# STM32F1_DHT11_UART.net
KiCad netlist of a schematic drawn in Altium Designer
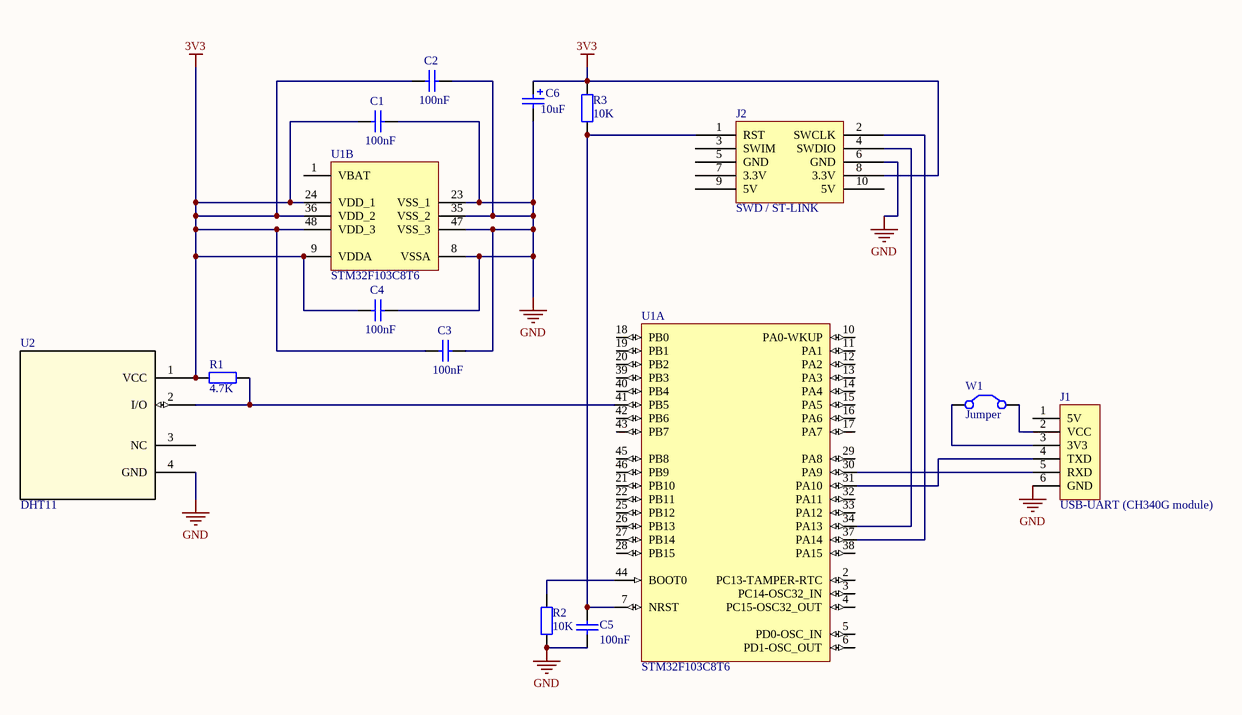
[diagram p0: STM32F1 DHT11 UART.SchDoc]

(export (version "E")
  (design (tool "Eeschema 10.0.6"))
  (components
    (comp (ref "C1")
      (value "100nF")
      (footprint "C1206")
      (description "Capacitor (Semiconductor SIM Model)")
      (fields (field (name "PUBLISHER") "Altium Limited"))
      (libsource (lib "Miscellaneous Devices") (part "Cap Semi"))
    )
    (comp (ref "C2")
      (value "100nF")
      (footprint "C1206")
      (description "Capacitor (Semiconductor SIM Model)")
      (fields (field (name "PUBLISHER") "Altium Limited"))
      (libsource (lib "Miscellaneous Devices") (part "Cap Semi"))
    )
    (comp (ref "C3")
      (value "100nF")
      (footprint "C1206")
      (description "Capacitor (Semiconductor SIM Model)")
      (fields (field (name "PUBLISHER") "Altium Limited"))
      (libsource (lib "Miscellaneous Devices") (part "Cap Semi"))
    )
    (comp (ref "C4")
      (value "100nF")
      (footprint "C1206")
      (description "Capacitor (Semiconductor SIM Model)")
      (fields (field (name "PUBLISHER") "Altium Limited"))
      (libsource (lib "Miscellaneous Devices") (part "Cap Semi"))
    )
    (comp (ref "C5")
      (value "100nF")
      (footprint "C1206")
      (description "Capacitor (Semiconductor SIM Model)")
      (fields (field (name "PUBLISHER") "Altium Limited"))
      (libsource (lib "Miscellaneous Devices") (part "Cap Semi"))
    )
    (comp (ref "C6")
      (value "~")
      (footprint "POLAR0.8")
      (description "Polarized Capacitor (Axial)")
      (fields (field (name "ALTIUM_UNNAMED_1") "10uF") (field (name "PUBLISHER") "Altium Limited"))
      (libsource (lib "Miscellaneous Devices") (part "Cap Pol2"))
    )
    (comp (ref "J1")
      (value "USB-UART (CH340G module)")
      (footprint "HDR1X6")
      (description "Header, 6-Pin")
      (fields (field (name "PUBLISHER") "Altium Limited"))
      (libsource (lib "Miscellaneous Connectors") (part "Header 6"))
    )
    (comp (ref "J2") (value "SWD / ST-LINK") (libsource (lib "Header 5X2H") (part "Header 5X2H")))
    (comp (ref "R1")
      (value "4.7K")
      (footprint "AXIAL-0.4")
      (description "Resistor")
      (fields (field (name "PUBLISHER") "Altium Limited"))
      (libsource (lib "") (part "Res2_1"))
    )
    (comp (ref "R2")
      (value "10K")
      (footprint "AXIAL-0.4")
      (fields (field (name "PUBLISHER") "Altium Limited"))
      (libsource (lib "Miscellaneous Devices") (part "Res2"))
    )
    (comp (ref "R3")
      (value "10K")
      (footprint "AXIAL-0.4")
      (fields (field (name "PUBLISHER") "Altium Limited"))
      (libsource (lib "Miscellaneous Devices") (part "Res2"))
    )
    (comp (ref "U1")
      (value "STM32F103C8T6")
      (footprint "STM-LQFP48_N")
      (libsource (lib "STMicroelectronics STM32 F1") (part "STM32F103C8T6"))
    )
    (comp (ref "U2")
      (value "DHT11")
      (footprint "TO-247-4_GAE")
      (description "No Description Available")
      (fields (field (name "COPYRIGHT") "Copyright (C) 2025 Ultra Librarian. All rights reserved."))
      (libsource (lib "DHT11") (part "DHT11"))
    )
    (comp (ref "W1")
      (value "Jumper")
      (footprint "RAD-0.2")
      (description "Jumper Wire")
      (fields (field (name "PUBLISHER") "Altium Limited"))
      (libsource (lib "Miscellaneous Devices") (part "Jumper"))
    )
  )
  (nets
    (net (code "1") (name "3V3") (class "Default")
      (node (ref "C1") (pin "1") (pinfunction "1_1") (pintype "passive"))
      (node (ref "C2") (pin "1") (pinfunction "1_1") (pintype "passive"))
      (node (ref "C3") (pin "1") (pinfunction "1_1") (pintype "passive"))
      (node (ref "C4") (pin "1") (pinfunction "1_1") (pintype "passive"))
      (node (ref "C6") (pin "1") (pinfunction "1_1") (pintype "passive"))
      (node (ref "J2") (pin "8") (pinfunction "3.3V_8") (pintype "passive"))
      (node (ref "R1") (pin "1") (pinfunction "1_1") (pintype "passive"))
      (node (ref "R3") (pin "1") (pinfunction "1_1") (pintype "passive"))
      (node (ref "U1") (pin "24") (pinfunction "VDD_1_24") (pintype "power_in"))
      (node (ref "U1") (pin "36") (pinfunction "VDD_2_36") (pintype "power_in"))
      (node (ref "U1") (pin "48") (pinfunction "VDD_3_48") (pintype "power_in"))
      (node (ref "U1") (pin "9") (pinfunction "VDDA_9") (pintype "power_in"))
      (node (ref "U2") (pin "1") (pinfunction "VCC_1") (pintype "power_in"))
    )
    (net (code "2") (name "GND") (class "Default")
      (node (ref "C1") (pin "2") (pinfunction "2_2") (pintype "passive"))
      (node (ref "C2") (pin "2") (pinfunction "2_2") (pintype "passive"))
      (node (ref "C3") (pin "2") (pinfunction "2_2") (pintype "passive"))
      (node (ref "C4") (pin "2") (pinfunction "2_2") (pintype "passive"))
      (node (ref "C5") (pin "2") (pinfunction "2_2") (pintype "passive"))
      (node (ref "C6") (pin "2") (pinfunction "2_2") (pintype "passive"))
      (node (ref "J1") (pin "6") (pinfunction "GND_6") (pintype "passive"))
      (node (ref "J2") (pin "6") (pinfunction "GND_6") (pintype "passive"))
      (node (ref "R2") (pin "2") (pinfunction "2_2") (pintype "passive"))
      (node (ref "U1") (pin "23") (pinfunction "VSS_1_23") (pintype "power_in"))
      (node (ref "U1") (pin "35") (pinfunction "VSS_2_35") (pintype "power_in"))
      (node (ref "U1") (pin "47") (pinfunction "VSS_3_47") (pintype "power_in"))
      (node (ref "U1") (pin "8") (pinfunction "VSSA_8") (pintype "power_in"))
      (node (ref "U2") (pin "4") (pinfunction "GND_4") (pintype "power_in"))
    )
    (net (code "3") (name "Net-(J1-3V3)") (class "Default")
      (node (ref "J1") (pin "3") (pinfunction "3V3_3") (pintype "passive"))
      (node (ref "W1") (pin "1") (pinfunction "C1_1") (pintype "passive"))
    )
    (net (code "4") (name "Net-(J1-RXD)") (class "Default")
      (node (ref "J1") (pin "5") (pinfunction "RXD_5") (pintype "passive"))
      (node (ref "U1") (pin "30") (pinfunction "PA9_30") (pintype "bidirectional"))
    )
    (net (code "5") (name "Net-(J1-TXD)") (class "Default")
      (node (ref "J1") (pin "4") (pinfunction "TXD_4") (pintype "passive"))
      (node (ref "U1") (pin "31") (pinfunction "PA10_31") (pintype "bidirectional"))
    )
    (net (code "6") (name "Net-(J1-VCC)") (class "Default")
      (node (ref "J1") (pin "2") (pinfunction "VCC_2") (pintype "passive"))
      (node (ref "W1") (pin "2") (pinfunction "C2_2") (pintype "passive"))
    )
    (net (code "7") (name "Net-(J2-RST)") (class "Default")
      (node (ref "C5") (pin "1") (pinfunction "1_1") (pintype "passive"))
      (node (ref "J2") (pin "1") (pinfunction "RST_1") (pintype "passive"))
      (node (ref "R3") (pin "2") (pinfunction "2_2") (pintype "passive"))
      (node (ref "U1") (pin "7") (pinfunction "NRST_7") (pintype "bidirectional"))
    )
    (net (code "8") (name "Net-(J2-SWCLK)") (class "Default")
      (node (ref "J2") (pin "2") (pinfunction "SWCLK_2") (pintype "passive"))
      (node (ref "U1") (pin "37") (pinfunction "PA14_37") (pintype "bidirectional"))
    )
    (net (code "9") (name "Net-(J2-SWDIO)") (class "Default")
      (node (ref "J2") (pin "4") (pinfunction "SWDIO_4") (pintype "passive"))
      (node (ref "U1") (pin "34") (pinfunction "PA13_34") (pintype "bidirectional"))
    )
    (net (code "10") (name "Net-(U1A-BOOT0)") (class "Default")
      (node (ref "R2") (pin "1") (pinfunction "1_1") (pintype "passive"))
      (node (ref "U1") (pin "44") (pinfunction "BOOT0_44") (pintype "input"))
    )
    (net (code "11") (name "Net-(U1A-PB5)") (class "Default")
      (node (ref "R1") (pin "2") (pinfunction "2_2") (pintype "passive"))
      (node (ref "U1") (pin "41") (pinfunction "PB5_41") (pintype "bidirectional"))
      (node (ref "U2") (pin "2") (pinfunction "I/O_2") (pintype "bidirectional"))
    )
    (net (code "12") (name "unconnected-(J1-5V-Pad1)") (class "Default")
      (node (ref "J1") (pin "1") (pinfunction "5V_1") (pintype "passive"))
    )
    (net (code "13") (name "unconnected-(J2-3.3V-Pad7)") (class "Default")
      (node (ref "J2") (pin "7") (pinfunction "3.3V_7") (pintype "passive"))
    )
    (net (code "14") (name "unconnected-(J2-5V-Pad9)") (class "Default")
      (node (ref "J2") (pin "9") (pinfunction "5V_9") (pintype "passive"))
    )
    (net (code "15") (name "unconnected-(J2-5V-Pad10)") (class "Default")
      (node (ref "J2") (pin "10") (pinfunction "5V_10") (pintype "passive"))
    )
    (net (code "16") (name "unconnected-(J2-GND-Pad5)") (class "Default")
      (node (ref "J2") (pin "5") (pinfunction "GND_5") (pintype "passive"))
    )
    (net (code "17") (name "unconnected-(J2-SWIM-Pad3)") (class "Default")
      (node (ref "J2") (pin "3") (pinfunction "SWIM_3") (pintype "passive"))
    )
    (net (code "18") (name "unconnected-(U1A-PA0-WKUP-Pad10)") (class "Default")
      (node (ref "U1") (pin "10") (pinfunction "PA0-WKUP_10") (pintype "bidirectional+no_connect"))
    )
    (net (code "19") (name "unconnected-(U1A-PA1-Pad11)") (class "Default")
      (node (ref "U1") (pin "11") (pinfunction "PA1_11") (pintype "bidirectional+no_connect"))
    )
    (net (code "20") (name "unconnected-(U1A-PA2-Pad12)") (class "Default")
      (node (ref "U1") (pin "12") (pinfunction "PA2_12") (pintype "bidirectional+no_connect"))
    )
    (net (code "21") (name "unconnected-(U1A-PA3-Pad13)") (class "Default")
      (node (ref "U1") (pin "13") (pinfunction "PA3_13") (pintype "bidirectional+no_connect"))
    )
    (net (code "22") (name "unconnected-(U1A-PA4-Pad14)") (class "Default")
      (node (ref "U1") (pin "14") (pinfunction "PA4_14") (pintype "bidirectional+no_connect"))
    )
    (net (code "23") (name "unconnected-(U1A-PA5-Pad15)") (class "Default")
      (node (ref "U1") (pin "15") (pinfunction "PA5_15") (pintype "bidirectional+no_connect"))
    )
    (net (code "24") (name "unconnected-(U1A-PA6-Pad16)") (class "Default")
      (node (ref "U1") (pin "16") (pinfunction "PA6_16") (pintype "bidirectional+no_connect"))
    )
    (net (code "25") (name "unconnected-(U1A-PA7-Pad17)") (class "Default")
      (node (ref "U1") (pin "17") (pinfunction "PA7_17") (pintype "bidirectional+no_connect"))
    )
    (net (code "26") (name "unconnected-(U1A-PA8-Pad29)") (class "Default")
      (node (ref "U1") (pin "29") (pinfunction "PA8_29") (pintype "bidirectional+no_connect"))
    )
    (net (code "27") (name "unconnected-(U1A-PA11-Pad32)") (class "Default")
      (node (ref "U1") (pin "32") (pinfunction "PA11_32") (pintype "bidirectional+no_connect"))
    )
    (net (code "28") (name "unconnected-(U1A-PA12-Pad33)") (class "Default")
      (node (ref "U1") (pin "33") (pinfunction "PA12_33") (pintype "bidirectional+no_connect"))
    )
    (net (code "29") (name "unconnected-(U1A-PA15-Pad38)") (class "Default")
      (node (ref "U1") (pin "38") (pinfunction "PA15_38") (pintype "bidirectional+no_connect"))
    )
    (net (code "30") (name "unconnected-(U1A-PB0-Pad18)") (class "Default")
      (node (ref "U1") (pin "18") (pinfunction "PB0_18") (pintype "bidirectional+no_connect"))
    )
    (net (code "31") (name "unconnected-(U1A-PB1-Pad19)") (class "Default")
      (node (ref "U1") (pin "19") (pinfunction "PB1_19") (pintype "bidirectional+no_connect"))
    )
    (net (code "32") (name "unconnected-(U1A-PB2-Pad20)") (class "Default")
      (node (ref "U1") (pin "20") (pinfunction "PB2_20") (pintype "bidirectional+no_connect"))
    )
    (net (code "33") (name "unconnected-(U1A-PB3-Pad39)") (class "Default")
      (node (ref "U1") (pin "39") (pinfunction "PB3_39") (pintype "bidirectional+no_connect"))
    )
    (net (code "34") (name "unconnected-(U1A-PB4-Pad40)") (class "Default")
      (node (ref "U1") (pin "40") (pinfunction "PB4_40") (pintype "bidirectional+no_connect"))
    )
    (net (code "35") (name "unconnected-(U1A-PB6-Pad42)") (class "Default")
      (node (ref "U1") (pin "42") (pinfunction "PB6_42") (pintype "bidirectional+no_connect"))
    )
    (net (code "36") (name "unconnected-(U1A-PB7-Pad43)") (class "Default")
      (node (ref "U1") (pin "43") (pinfunction "PB7_43") (pintype "bidirectional+no_connect"))
    )
    (net (code "37") (name "unconnected-(U1A-PB8-Pad45)") (class "Default")
      (node (ref "U1") (pin "45") (pinfunction "PB8_45") (pintype "bidirectional+no_connect"))
    )
    (net (code "38") (name "unconnected-(U1A-PB9-Pad46)") (class "Default")
      (node (ref "U1") (pin "46") (pinfunction "PB9_46") (pintype "bidirectional+no_connect"))
    )
    (net (code "39") (name "unconnected-(U1A-PB10-Pad21)") (class "Default")
      (node (ref "U1") (pin "21") (pinfunction "PB10_21") (pintype "bidirectional+no_connect"))
    )
    (net (code "40") (name "unconnected-(U1A-PB11-Pad22)") (class "Default")
      (node (ref "U1") (pin "22") (pinfunction "PB11_22") (pintype "bidirectional+no_connect"))
    )
    (net (code "41") (name "unconnected-(U1A-PB12-Pad25)") (class "Default")
      (node (ref "U1") (pin "25") (pinfunction "PB12_25") (pintype "bidirectional+no_connect"))
    )
    (net (code "42") (name "unconnected-(U1A-PB13-Pad26)") (class "Default")
      (node (ref "U1") (pin "26") (pinfunction "PB13_26") (pintype "bidirectional+no_connect"))
    )
    (net (code "43") (name "unconnected-(U1A-PB14-Pad27)") (class "Default")
      (node (ref "U1") (pin "27") (pinfunction "PB14_27") (pintype "bidirectional+no_connect"))
    )
    (net (code "44") (name "unconnected-(U1A-PB15-Pad28)") (class "Default")
      (node (ref "U1") (pin "28") (pinfunction "PB15_28") (pintype "bidirectional+no_connect"))
    )
    (net (code "45") (name "unconnected-(U1A-PC13-TAMPER-RTC-Pad2)") (class "Default")
      (node (ref "U1") (pin "2") (pinfunction "PC13-TAMPER-RTC_2") (pintype "bidirectional+no_connect"))
    )
    (net (code "46") (name "unconnected-(U1A-PC14-OSC32_IN-Pad3)") (class "Default")
      (node (ref "U1") (pin "3") (pinfunction "PC14-OSC32_IN_3") (pintype "bidirectional+no_connect"))
    )
    (net (code "47") (name "unconnected-(U1A-PC15-OSC32_OUT-Pad4)") (class "Default")
      (node (ref "U1") (pin "4") (pinfunction "PC15-OSC32_OUT_4") (pintype "bidirectional+no_connect"))
    )
    (net (code "48") (name "unconnected-(U1A-PD0-OSC_IN-Pad5)") (class "Default")
      (node (ref "U1") (pin "5") (pinfunction "PD0-OSC_IN_5") (pintype "bidirectional+no_connect"))
    )
    (net (code "49") (name "unconnected-(U1A-PD1-OSC_OUT-Pad6)") (class "Default")
      (node (ref "U1") (pin "6") (pinfunction "PD1-OSC_OUT_6") (pintype "bidirectional+no_connect"))
    )
    (net (code "50") (name "unconnected-(U1B-VBAT-Pad1)") (class "Default")
      (node (ref "U1") (pin "1") (pinfunction "VBAT_1") (pintype "power_in"))
    )
    (net (code "51") (name "unconnected-(U2-NC-Pad3)") (class "Default")
      (node (ref "U2") (pin "3") (pinfunction "NC_3") (pintype "passive"))
    )
  )
)
